# OTHER.net
KiCad netlist of a schematic drawn in Altium Designer
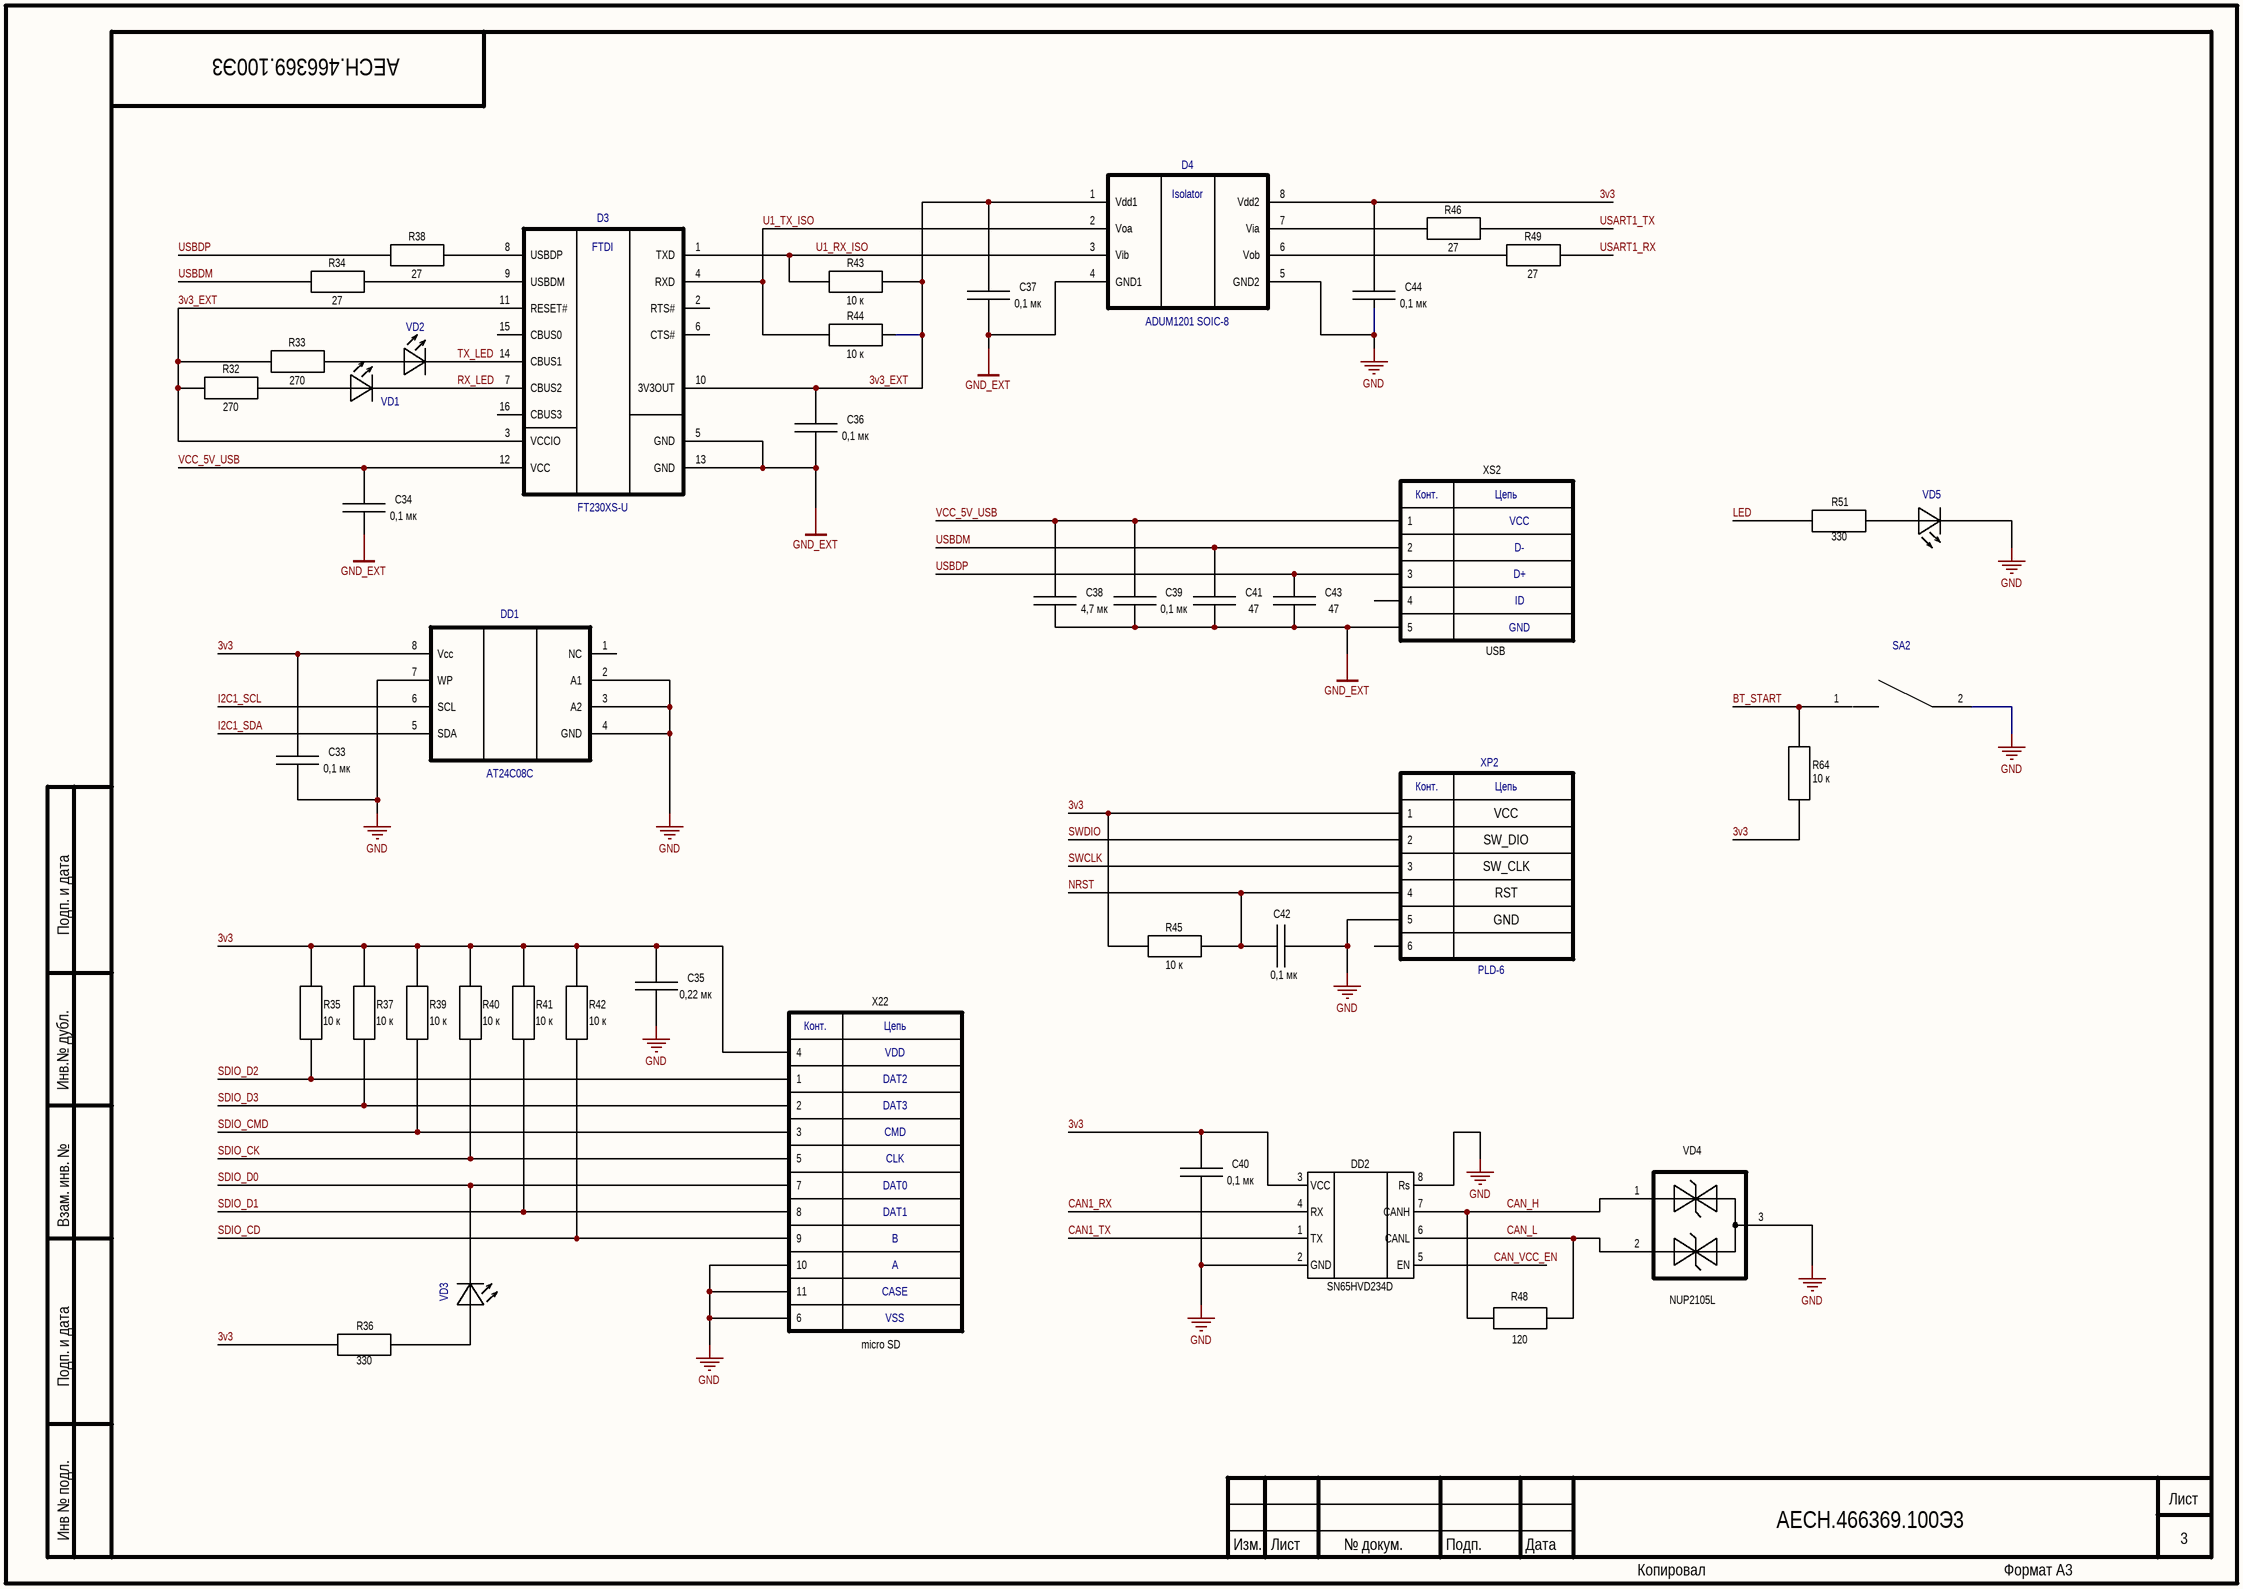
[diagram p0: OTHER.SchDoc]

(export (version "E")
  (design (tool "Eeschema 10.0.6"))
  (components
    (comp (ref "C33")
      (value "0,1 мк")
      (footprint "C0603")
      (fields
        (field (name "TOLERANCE") "±10%")
        (field (name "VOLTAGE") "50 В")
        (field (name "PARTNUMBER") "GRM188R71H104KA93D")
      )
      (libsource (lib "5ko") (part "C"))
    )
    (comp (ref "C34")
      (value "0,1 мк")
      (footprint "C0603")
      (fields
        (field (name "TOLERANCE") "±10%")
        (field (name "VOLTAGE") "50 В")
        (field (name "PARTNUMBER") "GRM188R71H104KA93D")
      )
      (libsource (lib "5ko") (part "C"))
    )
    (comp (ref "C35")
      (value "0,22 мк")
      (footprint "C0603")
      (fields
        (field (name "TOLERANCE") "±10%")
        (field (name "VOLTAGE") "25 В")
        (field (name "PARTNUMBER") "GRM188R71E224KA88D")
      )
      (libsource (lib "5ko") (part "C"))
    )
    (comp (ref "C36")
      (value "0,1 мк")
      (footprint "C0603")
      (fields
        (field (name "TOLERANCE") "±10%")
        (field (name "VOLTAGE") "50 В")
        (field (name "PARTNUMBER") "GRM188R71H104KA93D")
      )
      (libsource (lib "5ko") (part "C"))
    )
    (comp (ref "C37")
      (value "0,1 мк")
      (footprint "C0603")
      (fields
        (field (name "TOLERANCE") "±10%")
        (field (name "VOLTAGE") "50 В")
        (field (name "PARTNUMBER") "GRM188R71H104KA93D")
      )
      (libsource (lib "5ko") (part "C"))
    )
    (comp (ref "C38")
      (value "4,7 мк")
      (footprint "C0603")
      (fields
        (field (name "TOLERANCE") "±10%")
        (field (name "VOLTAGE") "16 В")
        (field (name "PARTNUMBER") "GRM188Z71C475KE21D")
      )
      (libsource (lib "5ko") (part "C"))
    )
    (comp (ref "C39")
      (value "0,1 мк")
      (footprint "C0603")
      (fields
        (field (name "TOLERANCE") "±10%")
        (field (name "VOLTAGE") "50 В")
        (field (name "PARTNUMBER") "GRM188R71H104KA93D")
      )
      (libsource (lib "5ko") (part "C"))
    )
    (comp (ref "C40")
      (value "0,1 мк")
      (footprint "C0603")
      (fields
        (field (name "TOLERANCE") "±10%")
        (field (name "VOLTAGE") "50 В")
        (field (name "PARTNUMBER") "GRM188R71H104KA93D")
      )
      (libsource (lib "5ko") (part "C"))
    )
    (comp (ref "C41")
      (value "47")
      (footprint "C0603")
      (fields
        (field (name "TOLERANCE") "±10%")
        (field (name "VOLTAGE") "50 В")
        (field (name "PARTNUMBER") "GRM1885C1H470FA01D")
      )
      (libsource (lib "5ko") (part "C"))
    )
    (comp (ref "C42")
      (value "0,1 мк")
      (footprint "C0603")
      (fields
        (field (name "TOLERANCE") "±10%")
        (field (name "VOLTAGE") "50 В")
        (field (name "PARTNUMBER") "GRM188R71H104KA93D")
      )
      (libsource (lib "5ko") (part "C"))
    )
    (comp (ref "C43")
      (value "47")
      (footprint "C0603")
      (fields
        (field (name "TOLERANCE") "±10%")
        (field (name "VOLTAGE") "50 В")
        (field (name "PARTNUMBER") "GRM1885C1H470FA01D")
      )
      (libsource (lib "5ko") (part "C"))
    )
    (comp (ref "C44")
      (value "0,1 мк")
      (footprint "C0603")
      (fields
        (field (name "TOLERANCE") "±10%")
        (field (name "VOLTAGE") "50 В")
        (field (name "PARTNUMBER") "GRM188R71H104KA93D")
      )
      (libsource (lib "5ko") (part "C"))
    )
    (comp (ref "D3") (value "FT230XS-U") (footprint "SSOP-16") (libsource (lib "5ko") (part "FT230XS-U")))
    (comp (ref "D4") (value "ADUM1201 SOIC-8") (footprint "SOIC8") (libsource (lib "5ko") (part "ADUM1201")))
    (comp (ref "DD1") (value "AT24C08C") (footprint "SOIC8") (libsource (lib "5ko") (part "AT24C0xC")))
    (comp (ref "DD2")
      (value "SN65HVD234D")
      (footprint "SOIC8")
      (description "CAN")
      (libsource (lib "5ko") (part "SN65HVD234D"))
    )
    (comp (ref "R32")
      (value "270")
      (footprint "R0603")
      (fields
        (field (name "TOLERANCE") "±5%")
        (field (name "POWER") "0.1 Вт")
        (field (name "PARTNUMBER") "RC0603JR-07270RL")
      )
      (libsource (lib "5ko") (part "R"))
    )
    (comp (ref "R33")
      (value "270")
      (footprint "R0603")
      (fields
        (field (name "TOLERANCE") "±5%")
        (field (name "POWER") "0.1 Вт")
        (field (name "PARTNUMBER") "RC0603JR-07270RL")
      )
      (libsource (lib "5ko") (part "R"))
    )
    (comp (ref "R34")
      (value "27")
      (footprint "R0603")
      (fields
        (field (name "TOLERANCE") "±5%")
        (field (name "POWER") "0.1 Вт")
        (field (name "PARTNUMBER") "RC0603JR-0727RL")
      )
      (libsource (lib "5ko") (part "R"))
    )
    (comp (ref "R35")
      (value "10 к")
      (footprint "R0603")
      (fields
        (field (name "TOLERANCE") "±5%")
        (field (name "POWER") "0.1 Вт")
        (field (name "PARTNUMBER") "RC0603JR-0710KL")
      )
      (libsource (lib "5ko") (part "R"))
    )
    (comp (ref "R36")
      (value "330")
      (footprint "R0603")
      (fields
        (field (name "TOLERANCE") "±5%")
        (field (name "POWER") "0.1 Вт")
        (field (name "PARTNUMBER") "RC0603JR-07330RL")
      )
      (libsource (lib "5ko") (part "R"))
    )
    (comp (ref "R37")
      (value "10 к")
      (footprint "R0603")
      (fields
        (field (name "TOLERANCE") "±5%")
        (field (name "POWER") "0.1 Вт")
        (field (name "PARTNUMBER") "RC0603JR-0710KL")
      )
      (libsource (lib "5ko") (part "R"))
    )
    (comp (ref "R38")
      (value "27")
      (footprint "R0603")
      (fields
        (field (name "TOLERANCE") "±5%")
        (field (name "POWER") "0.1 Вт")
        (field (name "PARTNUMBER") "RC0603JR-0727RL")
      )
      (libsource (lib "5ko") (part "R"))
    )
    (comp (ref "R39")
      (value "10 к")
      (footprint "R0603")
      (fields
        (field (name "TOLERANCE") "±5%")
        (field (name "POWER") "0.1 Вт")
        (field (name "PARTNUMBER") "RC0603JR-0710KL")
      )
      (libsource (lib "5ko") (part "R"))
    )
    (comp (ref "R40")
      (value "10 к")
      (footprint "R0603")
      (fields
        (field (name "TOLERANCE") "±5%")
        (field (name "POWER") "0.1 Вт")
        (field (name "PARTNUMBER") "RC0603JR-0710KL")
      )
      (libsource (lib "5ko") (part "R"))
    )
    (comp (ref "R41")
      (value "10 к")
      (footprint "R0603")
      (fields
        (field (name "TOLERANCE") "±5%")
        (field (name "POWER") "0.1 Вт")
        (field (name "PARTNUMBER") "RC0603JR-0710KL")
      )
      (libsource (lib "5ko") (part "R"))
    )
    (comp (ref "R42")
      (value "10 к")
      (footprint "R0603")
      (fields
        (field (name "TOLERANCE") "±5%")
        (field (name "POWER") "0.1 Вт")
        (field (name "PARTNUMBER") "RC0603JR-0710KL")
      )
      (libsource (lib "5ko") (part "R"))
    )
    (comp (ref "R43")
      (value "10 к")
      (footprint "R0603")
      (fields
        (field (name "TOLERANCE") "±5%")
        (field (name "POWER") "0.1 Вт")
        (field (name "PARTNUMBER") "RC0603JR-0710KL")
      )
      (libsource (lib "5ko") (part "R"))
    )
    (comp (ref "R44")
      (value "10 к")
      (footprint "R0603")
      (fields
        (field (name "TOLERANCE") "±5%")
        (field (name "POWER") "0.1 Вт")
        (field (name "PARTNUMBER") "RC0603JR-0710KL")
      )
      (libsource (lib "5ko") (part "R"))
    )
    (comp (ref "R45")
      (value "10 к")
      (footprint "R0603")
      (fields
        (field (name "TOLERANCE") "±5%")
        (field (name "POWER") "0.1 Вт")
        (field (name "PARTNUMBER") "RC0603JR-0710KL")
      )
      (libsource (lib "5ko") (part "R"))
    )
    (comp (ref "R46")
      (value "27")
      (footprint "R0603")
      (fields
        (field (name "TOLERANCE") "±5%")
        (field (name "POWER") "0.1 Вт")
        (field (name "PARTNUMBER") "RC0603JR-0727RL")
      )
      (libsource (lib "5ko") (part "R"))
    )
    (comp (ref "R48")
      (value "120")
      (footprint "R1206")
      (fields
        (field (name "TOLERANCE") "±5%")
        (field (name "POWER") "0.25 Вт")
        (field (name "PARTNUMBER") "RC1206JR-13120RL")
      )
      (libsource (lib "5ko") (part "R"))
    )
    (comp (ref "R49")
      (value "27")
      (footprint "R0603")
      (fields
        (field (name "TOLERANCE") "±5%")
        (field (name "POWER") "0.1 Вт")
        (field (name "PARTNUMBER") "RC0603JR-0727RL")
      )
      (libsource (lib "5ko") (part "R"))
    )
    (comp (ref "R51")
      (value "330")
      (footprint "R0603")
      (fields
        (field (name "TOLERANCE") "±5%")
        (field (name "POWER") "0.1 Вт")
        (field (name "PARTNUMBER") "RC0603JR-07330RL")
      )
      (libsource (lib "5ko") (part "R"))
    )
    (comp (ref "R64")
      (value "10 к")
      (footprint "R0603")
      (fields
        (field (name "TOLERANCE") "±5%")
        (field (name "POWER") "0.1 Вт")
        (field (name "PARTNUMBER") "RC0603JR-0710KL")
      )
      (libsource (lib "5ko") (part "R"))
    )
    (comp (ref "SA2") (value "Button") (footprint "KLS7_6x6") (libsource (lib "5ko") (part "Button")))
    (comp (ref "VD1") (value "LED") (footprint "LED_0603_YELLOW") (libsource (lib "5ko") (part "LED")))
    (comp (ref "VD2") (value "LED") (footprint "LED_0603_GREEN") (libsource (lib "5ko") (part "LED")))
    (comp (ref "VD3") (value "LED") (footprint "LED_0603_BLUE") (libsource (lib "5ko") (part "LED")))
    (comp (ref "VD4") (value "NUP2105L") (footprint "SOT-23") (libsource (lib "5ko") (part "NUP2105L")))
    (comp (ref "VD5") (value "LED") (footprint "LED_0603_RED") (libsource (lib "5ko") (part "LED")))
    (comp (ref "X22")
      (value "micro SD")
      (footprint "DM3AT-SF-PEJM5")
      (libsource (lib "5ko") (part "microSD"))
    )
    (comp (ref "XP2")
      (value "PLD-6")
      (footprint "PLD-6")
      (fields (field (name "PARTNUMBER") "PLD-6"))
      (libsource (lib "5ko") (part "6pin"))
    )
    (comp (ref "XS2") (value "USB") (footprint "USB_MICRO_1981568-1") (libsource (lib "5ko") (part "USB")))
  )
  (nets
    (net (code "1") (name "/3v3") (class "Default")
      (node (ref "C33") (pin "1") (pinfunction "1_1") (pintype "passive"))
      (node (ref "C35") (pin "1") (pinfunction "1_1") (pintype "passive"))
      (node (ref "C40") (pin "1") (pinfunction "1_1") (pintype "passive"))
      (node (ref "C44") (pin "1") (pinfunction "1_1") (pintype "passive"))
      (node (ref "D4") (pin "8") (pinfunction "Vdd2_8") (pintype "passive"))
      (node (ref "DD1") (pin "8") (pinfunction "Vcc_8") (pintype "passive"))
      (node (ref "DD2") (pin "3") (pinfunction "VCC_3") (pintype "passive"))
      (node (ref "R35") (pin "2") (pinfunction "2_2") (pintype "passive"))
      (node (ref "R36") (pin "2") (pinfunction "2_2") (pintype "passive"))
      (node (ref "R37") (pin "2") (pinfunction "2_2") (pintype "passive"))
      (node (ref "R39") (pin "2") (pinfunction "2_2") (pintype "passive"))
      (node (ref "R40") (pin "2") (pinfunction "2_2") (pintype "passive"))
      (node (ref "R41") (pin "2") (pinfunction "2_2") (pintype "passive"))
      (node (ref "R42") (pin "2") (pinfunction "2_2") (pintype "passive"))
      (node (ref "R45") (pin "1") (pinfunction "1_1") (pintype "passive"))
      (node (ref "R64") (pin "1") (pinfunction "1_1") (pintype "passive"))
      (node (ref "X22") (pin "4") (pinfunction "4_4") (pintype "passive"))
      (node (ref "XP2") (pin "1") (pinfunction "1_1") (pintype "passive"))
    )
    (net (code "2") (name "/3v3_EXT") (class "Default")
      (node (ref "C36") (pin "1") (pinfunction "1_1") (pintype "passive"))
      (node (ref "C37") (pin "1") (pinfunction "1_1") (pintype "passive"))
      (node (ref "D3") (pin "10") (pinfunction "3V3OUT_10") (pintype "passive"))
      (node (ref "D3") (pin "11") (pinfunction "RESET#_11") (pintype "passive"))
      (node (ref "D3") (pin "3") (pinfunction "VCCIO_3") (pintype "passive"))
      (node (ref "D4") (pin "1") (pinfunction "Vdd1_1") (pintype "passive"))
      (node (ref "R32") (pin "1") (pinfunction "1_1") (pintype "passive"))
      (node (ref "R33") (pin "1") (pinfunction "1_1") (pintype "passive"))
      (node (ref "R43") (pin "2") (pinfunction "2_2") (pintype "passive"))
      (node (ref "R44") (pin "2") (pinfunction "2_2") (pintype "passive"))
    )
    (net (code "3") (name "/BT_START") (class "Default")
      (node (ref "R64") (pin "2") (pinfunction "2_2") (pintype "passive"))
      (node (ref "SA2") (pin "1") (pintype "passive"))
    )
    (net (code "4") (name "/CAN1_RX") (class "Default")
      (node (ref "DD2") (pin "4") (pinfunction "RX_4") (pintype "passive"))
    )
    (net (code "5") (name "/CAN1_TX") (class "Default")
      (node (ref "DD2") (pin "1") (pinfunction "TX_1") (pintype "passive"))
    )
    (net (code "6") (name "/CAN_H") (class "Default")
      (node (ref "DD2") (pin "7") (pinfunction "CANH_7") (pintype "passive"))
      (node (ref "R48") (pin "1") (pinfunction "1_1") (pintype "passive"))
      (node (ref "VD4") (pin "1") (pinfunction "A_1") (pintype "passive"))
    )
    (net (code "7") (name "/CAN_L") (class "Default")
      (node (ref "DD2") (pin "6") (pinfunction "CANL_6") (pintype "passive"))
      (node (ref "R48") (pin "2") (pinfunction "2_2") (pintype "passive"))
      (node (ref "VD4") (pin "2") (pinfunction "C_2") (pintype "passive"))
    )
    (net (code "8") (name "/CAN_VCC_EN") (class "Default")
      (node (ref "DD2") (pin "5") (pinfunction "EN_5") (pintype "passive"))
    )
    (net (code "9") (name "/I2C1_SCL") (class "Default")
      (node (ref "DD1") (pin "6") (pinfunction "SCL_6") (pintype "passive"))
    )
    (net (code "10") (name "/I2C1_SDA") (class "Default")
      (node (ref "DD1") (pin "5") (pinfunction "SDA_5") (pintype "passive"))
    )
    (net (code "11") (name "/LED") (class "Default")
      (node (ref "R51") (pin "2") (pinfunction "2_2") (pintype "passive"))
    )
    (net (code "12") (name "/NRST") (class "Default")
      (node (ref "C42") (pin "1") (pinfunction "1_1") (pintype "passive"))
      (node (ref "R45") (pin "2") (pinfunction "2_2") (pintype "passive"))
      (node (ref "XP2") (pin "4") (pinfunction "4_4") (pintype "passive"))
    )
    (net (code "13") (name "/RX_LED") (class "Default")
      (node (ref "D3") (pin "7") (pinfunction "CBUS2_7") (pintype "passive"))
      (node (ref "VD1") (pin "2") (pinfunction "C_2") (pintype "passive"))
    )
    (net (code "14") (name "/SDIO_CD") (class "Default")
      (node (ref "R42") (pin "1") (pinfunction "1_1") (pintype "passive"))
      (node (ref "X22") (pin "9") (pinfunction "9_9") (pintype "passive"))
    )
    (net (code "15") (name "/SDIO_CK") (class "Default")
      (node (ref "R40") (pin "1") (pinfunction "1_1") (pintype "passive"))
      (node (ref "X22") (pin "5") (pinfunction "5_5") (pintype "passive"))
    )
    (net (code "16") (name "/SDIO_CMD") (class "Default")
      (node (ref "R39") (pin "1") (pinfunction "1_1") (pintype "passive"))
      (node (ref "X22") (pin "3") (pinfunction "3_3") (pintype "passive"))
    )
    (net (code "17") (name "/SDIO_D0") (class "Default")
      (node (ref "VD3") (pin "2") (pinfunction "C_2") (pintype "passive"))
      (node (ref "X22") (pin "7") (pinfunction "7_7") (pintype "passive"))
    )
    (net (code "18") (name "/SDIO_D1") (class "Default")
      (node (ref "R41") (pin "1") (pinfunction "1_1") (pintype "passive"))
      (node (ref "X22") (pin "8") (pinfunction "8_8") (pintype "passive"))
    )
    (net (code "19") (name "/SDIO_D2") (class "Default")
      (node (ref "R35") (pin "1") (pinfunction "1_1") (pintype "passive"))
      (node (ref "X22") (pin "1") (pinfunction "1_1") (pintype "passive"))
    )
    (net (code "20") (name "/SDIO_D3") (class "Default")
      (node (ref "R37") (pin "1") (pinfunction "1_1") (pintype "passive"))
      (node (ref "X22") (pin "2") (pinfunction "2_2") (pintype "passive"))
    )
    (net (code "21") (name "/SWCLK") (class "Default")
      (node (ref "XP2") (pin "3") (pinfunction "3_3") (pintype "passive"))
    )
    (net (code "22") (name "/SWDIO") (class "Default")
      (node (ref "XP2") (pin "2") (pinfunction "2_2") (pintype "passive"))
    )
    (net (code "23") (name "/TX_LED") (class "Default")
      (node (ref "D3") (pin "14") (pinfunction "CBUS1_14") (pintype "passive"))
      (node (ref "VD2") (pin "2") (pinfunction "C_2") (pintype "passive"))
    )
    (net (code "24") (name "/U1_RX_ISO") (class "Default")
      (node (ref "D3") (pin "1") (pinfunction "TXD_1") (pintype "passive"))
      (node (ref "D4") (pin "3") (pinfunction "Vib_3") (pintype "passive"))
      (node (ref "R43") (pin "1") (pinfunction "1_1") (pintype "passive"))
    )
    (net (code "25") (name "/U1_TX_ISO") (class "Default")
      (node (ref "D3") (pin "4") (pinfunction "RXD_4") (pintype "passive"))
      (node (ref "D4") (pin "2") (pinfunction "Voa_2") (pintype "passive"))
      (node (ref "R44") (pin "1") (pinfunction "1_1") (pintype "passive"))
    )
    (net (code "26") (name "/USART1_RX") (class "Default")
      (node (ref "R49") (pin "2") (pinfunction "2_2") (pintype "passive"))
    )
    (net (code "27") (name "/USART1_TX") (class "Default")
      (node (ref "R46") (pin "2") (pinfunction "2_2") (pintype "passive"))
    )
    (net (code "28") (name "/USBDM") (class "Default")
      (node (ref "C41") (pin "1") (pinfunction "1_1") (pintype "passive"))
      (node (ref "R34") (pin "1") (pinfunction "1_1") (pintype "passive"))
      (node (ref "XS2") (pin "2") (pinfunction "2_2") (pintype "passive"))
    )
    (net (code "29") (name "/USBDP") (class "Default")
      (node (ref "C43") (pin "1") (pinfunction "1_1") (pintype "passive"))
      (node (ref "R38") (pin "1") (pinfunction "1_1") (pintype "passive"))
      (node (ref "XS2") (pin "3") (pinfunction "3_3") (pintype "passive"))
    )
    (net (code "30") (name "/VCC_5V_USB") (class "Default")
      (node (ref "C34") (pin "1") (pinfunction "1_1") (pintype "passive"))
      (node (ref "C38") (pin "1") (pinfunction "1_1") (pintype "passive"))
      (node (ref "C39") (pin "1") (pinfunction "1_1") (pintype "passive"))
      (node (ref "D3") (pin "12") (pinfunction "VCC_12") (pintype "passive"))
      (node (ref "XS2") (pin "1") (pinfunction "1_1") (pintype "passive"))
    )
    (net (code "31") (name "GND") (class "Default")
      (node (ref "C33") (pin "2") (pinfunction "2_2") (pintype "passive"))
      (node (ref "C35") (pin "2") (pinfunction "2_2") (pintype "passive"))
      (node (ref "C40") (pin "2") (pinfunction "2_2") (pintype "passive"))
      (node (ref "C42") (pin "2") (pinfunction "2_2") (pintype "passive"))
      (node (ref "C44") (pin "2") (pinfunction "2_2") (pintype "passive"))
      (node (ref "D4") (pin "5") (pinfunction "GND2_5") (pintype "passive"))
      (node (ref "DD1") (pin "2") (pinfunction "A1_2") (pintype "passive"))
      (node (ref "DD1") (pin "3") (pinfunction "A2_3") (pintype "passive"))
      (node (ref "DD1") (pin "4") (pinfunction "GND_4") (pintype "passive"))
      (node (ref "DD1") (pin "7") (pinfunction "WP_7") (pintype "passive"))
      (node (ref "DD2") (pin "2") (pinfunction "GND_2") (pintype "passive"))
      (node (ref "DD2") (pin "8") (pinfunction "Rs_8") (pintype "passive"))
      (node (ref "SA2") (pin "2") (pintype "passive"))
      (node (ref "VD4") (pin "3") (pinfunction "AC_3") (pintype "passive"))
      (node (ref "VD5") (pin "2") (pinfunction "C_2") (pintype "passive"))
      (node (ref "X22") (pin "10") (pinfunction "10_10") (pintype "passive"))
      (node (ref "X22") (pin "11") (pinfunction "11_11") (pintype "passive"))
      (node (ref "X22") (pin "6") (pinfunction "6_6") (pintype "passive"))
      (node (ref "XP2") (pin "5") (pinfunction "5_5") (pintype "passive"))
    )
    (net (code "32") (name "GND_EXT") (class "Default")
      (node (ref "C34") (pin "2") (pinfunction "2_2") (pintype "passive"))
      (node (ref "C36") (pin "2") (pinfunction "2_2") (pintype "passive"))
      (node (ref "C37") (pin "2") (pinfunction "2_2") (pintype "passive"))
      (node (ref "C38") (pin "2") (pinfunction "2_2") (pintype "passive"))
      (node (ref "C39") (pin "2") (pinfunction "2_2") (pintype "passive"))
      (node (ref "C41") (pin "2") (pinfunction "2_2") (pintype "passive"))
      (node (ref "C43") (pin "2") (pinfunction "2_2") (pintype "passive"))
      (node (ref "D3") (pin "13") (pinfunction "GND_13") (pintype "passive"))
      (node (ref "D3") (pin "5") (pinfunction "GND_5") (pintype "passive"))
      (node (ref "D4") (pin "4") (pinfunction "GND1_4") (pintype "passive"))
      (node (ref "XS2") (pin "5") (pinfunction "5_5") (pintype "passive"))
    )
    (net (code "33") (name "Net-(D3-USBDM)") (class "Default")
      (node (ref "D3") (pin "9") (pinfunction "USBDM_9") (pintype "passive"))
      (node (ref "R34") (pin "2") (pinfunction "2_2") (pintype "passive"))
    )
    (net (code "34") (name "Net-(D3-USBDP)") (class "Default")
      (node (ref "D3") (pin "8") (pinfunction "USBDP_8") (pintype "passive"))
      (node (ref "R38") (pin "2") (pinfunction "2_2") (pintype "passive"))
    )
    (net (code "35") (name "Net-(D4-Via)") (class "Default")
      (node (ref "D4") (pin "7") (pinfunction "Via_7") (pintype "passive"))
      (node (ref "R46") (pin "1") (pinfunction "1_1") (pintype "passive"))
    )
    (net (code "36") (name "Net-(D4-Vob)") (class "Default")
      (node (ref "D4") (pin "6") (pinfunction "Vob_6") (pintype "passive"))
      (node (ref "R49") (pin "1") (pinfunction "1_1") (pintype "passive"))
    )
    (net (code "37") (name "Net-(VD1-A)") (class "Default")
      (node (ref "R32") (pin "2") (pinfunction "2_2") (pintype "passive"))
      (node (ref "VD1") (pin "1") (pinfunction "A_1") (pintype "passive"))
    )
    (net (code "38") (name "Net-(VD2-A)") (class "Default")
      (node (ref "R33") (pin "2") (pinfunction "2_2") (pintype "passive"))
      (node (ref "VD2") (pin "1") (pinfunction "A_1") (pintype "passive"))
    )
    (net (code "39") (name "Net-(VD3-A)") (class "Default")
      (node (ref "R36") (pin "1") (pinfunction "1_1") (pintype "passive"))
      (node (ref "VD3") (pin "1") (pinfunction "A_1") (pintype "passive"))
    )
    (net (code "40") (name "Net-(VD5-A)") (class "Default")
      (node (ref "R51") (pin "1") (pinfunction "1_1") (pintype "passive"))
      (node (ref "VD5") (pin "1") (pinfunction "A_1") (pintype "passive"))
    )
    (net (code "41") (name "unconnected-(D3-CBUS0-Pad15)") (class "Default")
      (node (ref "D3") (pin "15") (pinfunction "CBUS0_15") (pintype "passive"))
    )
    (net (code "42") (name "unconnected-(D3-CBUS3-Pad16)") (class "Default")
      (node (ref "D3") (pin "16") (pinfunction "CBUS3_16") (pintype "passive"))
    )
    (net (code "43") (name "unconnected-(D3-CTS#-Pad6)") (class "Default")
      (node (ref "D3") (pin "6") (pinfunction "CTS#_6") (pintype "passive"))
    )
    (net (code "44") (name "unconnected-(D3-RTS#-Pad2)") (class "Default")
      (node (ref "D3") (pin "2") (pinfunction "RTS#_2") (pintype "passive"))
    )
    (net (code "45") (name "unconnected-(DD1-NC-Pad1)") (class "Default")
      (node (ref "DD1") (pin "1") (pinfunction "NC_1") (pintype "passive"))
    )
    (net (code "46") (name "unconnected-(XP2-Pad6)") (class "Default")
      (node (ref "XP2") (pin "6") (pinfunction "6_6") (pintype "passive"))
    )
    (net (code "47") (name "unconnected-(XS2-Pad4)") (class "Default")
      (node (ref "XS2") (pin "4") (pinfunction "4_4") (pintype "passive"))
    )
  )
)
